# Endstops.net
KiCad netlist of a schematic drawn in Altium Designer
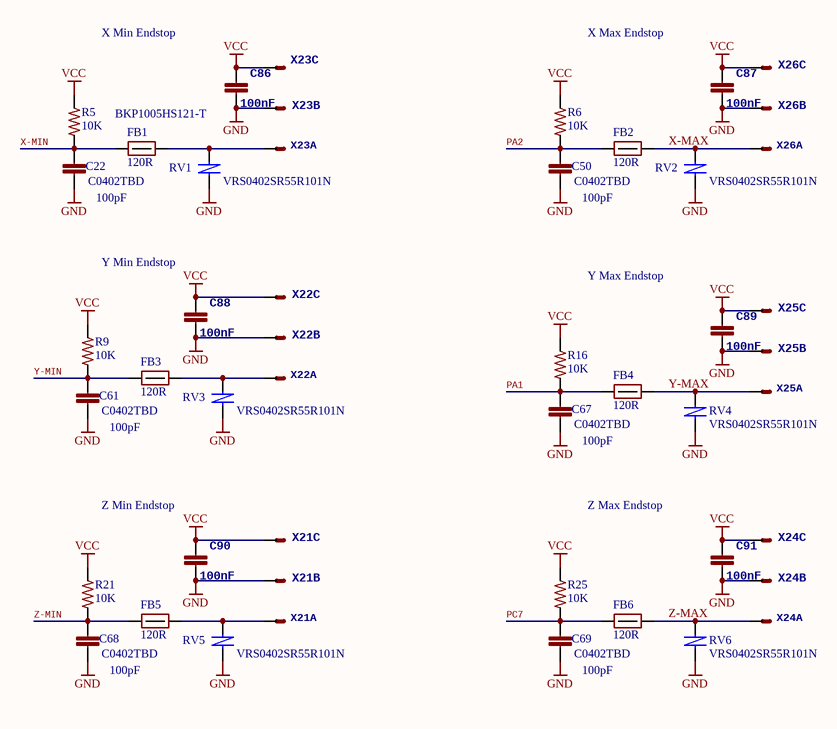
[diagram p0: Endstops.SchDoc]

(export (version "E")
  (design (tool "Eeschema 10.0.6"))
  (components
    (comp (ref "C22")
      (value "100pF")
      (footprint "C0402")
      (description "Capacitor Non Polarized")
      (fields
        (field (name "MANUFACTURER") "Murata")
        (field (name "ALTIUM_VALUE") "C0402TBD")
        (field (name "PUBLISHER") "UltiMachine")
      )
      (libsource (lib "3Delight") (part "C0402TBD"))
    )
    (comp (ref "C50")
      (value "100pF")
      (footprint "C0402")
      (description "Capacitor Non Polarized")
      (fields
        (field (name "MANUFACTURER") "Murata")
        (field (name "ALTIUM_VALUE") "C0402TBD")
        (field (name "PUBLISHER") "UltiMachine")
      )
      (libsource (lib "3Delight") (part "C0402TBD"))
    )
    (comp (ref "C61")
      (value "100pF")
      (footprint "C0402")
      (description "Capacitor Non Polarized")
      (fields
        (field (name "MANUFACTURER") "Murata")
        (field (name "ALTIUM_VALUE") "C0402TBD")
        (field (name "PUBLISHER") "UltiMachine")
      )
      (libsource (lib "3Delight") (part "C0402TBD"))
    )
    (comp (ref "C67")
      (value "100pF")
      (footprint "C0402")
      (description "Capacitor Non Polarized")
      (fields
        (field (name "MANUFACTURER") "Murata")
        (field (name "ALTIUM_VALUE") "C0402TBD")
        (field (name "PUBLISHER") "UltiMachine")
      )
      (libsource (lib "3Delight") (part "C0402TBD"))
    )
    (comp (ref "C68")
      (value "100pF")
      (footprint "C0402")
      (description "Capacitor Non Polarized")
      (fields
        (field (name "MANUFACTURER") "Murata")
        (field (name "ALTIUM_VALUE") "C0402TBD")
        (field (name "PUBLISHER") "UltiMachine")
      )
      (libsource (lib "3Delight") (part "C0402TBD"))
    )
    (comp (ref "C69")
      (value "100pF")
      (footprint "C0402")
      (description "Capacitor Non Polarized")
      (fields
        (field (name "MANUFACTURER") "Murata")
        (field (name "ALTIUM_VALUE") "C0402TBD")
        (field (name "PUBLISHER") "UltiMachine")
      )
      (libsource (lib "3Delight") (part "C0402TBD"))
    )
    (comp (ref "C86")
      (value "100nF")
      (footprint "C0402")
      (description "CAPACITOR, European symbol")
      (fields (field (name "MANUFACTURER") "Murata"))
      (libsource (lib "rcl") (part "C-EUC0402"))
    )
    (comp (ref "C87")
      (value "100nF")
      (footprint "C0402")
      (description "CAPACITOR, European symbol")
      (fields (field (name "MANUFACTURER") "Murata"))
      (libsource (lib "rcl") (part "C-EUC0402"))
    )
    (comp (ref "C88")
      (value "100nF")
      (footprint "C0402")
      (description "CAPACITOR, European symbol")
      (fields (field (name "MANUFACTURER") "Murata"))
      (libsource (lib "rcl") (part "C-EUC0402"))
    )
    (comp (ref "C89")
      (value "100nF")
      (footprint "C0402")
      (description "CAPACITOR, European symbol")
      (fields (field (name "MANUFACTURER") "Murata"))
      (libsource (lib "rcl") (part "C-EUC0402"))
    )
    (comp (ref "C90")
      (value "100nF")
      (footprint "C0402")
      (description "CAPACITOR, European symbol")
      (fields (field (name "MANUFACTURER") "Murata"))
      (libsource (lib "rcl") (part "C-EUC0402"))
    )
    (comp (ref "C91")
      (value "100nF")
      (footprint "C0402")
      (description "CAPACITOR, European symbol")
      (fields (field (name "MANUFACTURER") "Murata"))
      (libsource (lib "rcl") (part "C-EUC0402"))
    )
    (comp (ref "FB1")
      (value "120R")
      (footprint "R0402")
      (description "FERRITE BEAD 120 OHM 0402 1LN")
      (fields
        (field (name "MANUFACTURER") "Taiyo Yuden")
        (field (name "MANUFACTURER #") "BKP1005HS121-T")
        (field (name "PART") "FERRITE 120R 1A 0402")
      )
      (libsource (lib "Inductors_1") (part "FERRITE 120R 1A 0402"))
    )
    (comp (ref "FB2")
      (value "120R")
      (footprint "R0402")
      (description "FERRITE BEAD 120 OHM 0402 1LN")
      (fields (field (name "MANUFACTURER") "Taiyo Yuden") (field (name "PART") "FERRITE 120R 1A 0402"))
      (libsource (lib "Inductors_1") (part "FERRITE 120R 1A 0402"))
    )
    (comp (ref "FB3")
      (value "120R")
      (footprint "R0402")
      (description "FERRITE BEAD 120 OHM 0402 1LN")
      (fields (field (name "MANUFACTURER") "Taiyo Yuden") (field (name "PART") "FERRITE 120R 1A 0402"))
      (libsource (lib "Inductors_1") (part "FERRITE 120R 1A 0402"))
    )
    (comp (ref "FB4")
      (value "120R")
      (footprint "R0402")
      (description "FERRITE BEAD 120 OHM 0402 1LN")
      (fields (field (name "MANUFACTURER") "Taiyo Yuden") (field (name "PART") "FERRITE 120R 1A 0402"))
      (libsource (lib "Inductors_1") (part "FERRITE 120R 1A 0402"))
    )
    (comp (ref "FB5")
      (value "120R")
      (footprint "R0402")
      (description "FERRITE BEAD 120 OHM 0402 1LN")
      (fields (field (name "MANUFACTURER") "Taiyo Yuden") (field (name "PART") "FERRITE 120R 1A 0402"))
      (libsource (lib "Inductors_1") (part "FERRITE 120R 1A 0402"))
    )
    (comp (ref "FB6")
      (value "120R")
      (footprint "R0402")
      (description "FERRITE BEAD 120 OHM 0402 1LN")
      (fields (field (name "MANUFACTURER") "Taiyo Yuden") (field (name "PART") "FERRITE 120R 1A 0402"))
      (libsource (lib "Inductors_1") (part "FERRITE 120R 1A 0402"))
    )
    (comp (ref "R5")
      (value "10K")
      (footprint "R0402")
      (description "RES SMD 10K OHM 1% 1/16W 0402")
      (fields (field (name "MANUFACTURER") "Yageo") (field (name "PART") "10k 1% 0402"))
      (libsource (lib "3Delight") (part "RC0402FR-0710KP"))
    )
    (comp (ref "R6")
      (value "10K")
      (footprint "R0402")
      (description "RES SMD 10K OHM 1% 1/16W 0402")
      (fields (field (name "MANUFACTURER") "Yageo") (field (name "PART") "10k 1% 0402"))
      (libsource (lib "3Delight") (part "RC0402FR-0710KP"))
    )
    (comp (ref "R9")
      (value "10K")
      (footprint "R0402")
      (description "RES SMD 10K OHM 1% 1/16W 0402")
      (fields (field (name "MANUFACTURER") "Yageo") (field (name "PART") "10k 1% 0402"))
      (libsource (lib "3Delight") (part "RC0402FR-0710KP"))
    )
    (comp (ref "R16")
      (value "10K")
      (footprint "R0402")
      (description "RES SMD 10K OHM 1% 1/16W 0402")
      (fields (field (name "MANUFACTURER") "Yageo") (field (name "PART") "10k 1% 0402"))
      (libsource (lib "3Delight") (part "RC0402FR-0710KP"))
    )
    (comp (ref "R21")
      (value "10K")
      (footprint "R0402")
      (description "RES SMD 10K OHM 1% 1/16W 0402")
      (fields (field (name "MANUFACTURER") "Yageo") (field (name "PART") "10k 1% 0402"))
      (libsource (lib "3Delight") (part "RC0402FR-0710KP"))
    )
    (comp (ref "R25")
      (value "10K")
      (footprint "R0402")
      (description "RES SMD 10K OHM 1% 1/16W 0402")
      (fields (field (name "MANUFACTURER") "Yageo") (field (name "PART") "10k 1% 0402"))
      (libsource (lib "3Delight") (part "RC0402FR-0710KP"))
    )
    (comp (ref "RV1")
      (value "VRS0402SR55R101N")
      (footprint "C0402")
      (description "Multi-Layer Varistor")
      (fields
        (field (name "MANUFACTURER #") "VRS0402SR55R101N")
        (field (name "MANUFACTURER") "Yageo")
        (field (name "PART") "12V")
      )
      (libsource (lib "3Delight") (part "VRS0402SR55R101N"))
    )
    (comp (ref "RV2")
      (value "VRS0402SR55R101N")
      (footprint "C0402")
      (description "Multi-Layer Varistor")
      (fields
        (field (name "MANUFACTURER #") "VRS0402SR55R101N")
        (field (name "MANUFACTURER") "Yageo")
        (field (name "PART") "12V")
      )
      (libsource (lib "3Delight") (part "VRS0402SR55R101N"))
    )
    (comp (ref "RV3")
      (value "VRS0402SR55R101N")
      (footprint "C0402")
      (description "Multi-Layer Varistor")
      (fields
        (field (name "MANUFACTURER #") "VRS0402SR55R101N")
        (field (name "MANUFACTURER") "Yageo")
        (field (name "PART") "12V")
      )
      (libsource (lib "3Delight") (part "VRS0402SR55R101N"))
    )
    (comp (ref "RV4")
      (value "VRS0402SR55R101N")
      (footprint "C0402")
      (description "Multi-Layer Varistor")
      (fields
        (field (name "MANUFACTURER #") "VRS0402SR55R101N")
        (field (name "MANUFACTURER") "Yageo")
        (field (name "PART") "12V")
      )
      (libsource (lib "3Delight") (part "VRS0402SR55R101N"))
    )
    (comp (ref "RV5")
      (value "VRS0402SR55R101N")
      (footprint "C0402")
      (description "Multi-Layer Varistor")
      (fields
        (field (name "MANUFACTURER #") "VRS0402SR55R101N")
        (field (name "MANUFACTURER") "Yageo")
        (field (name "PART") "12V")
      )
      (libsource (lib "3Delight") (part "VRS0402SR55R101N"))
    )
    (comp (ref "RV6")
      (value "VRS0402SR55R101N")
      (footprint "C0402")
      (description "Multi-Layer Varistor")
      (fields
        (field (name "MANUFACTURER #") "VRS0402SR55R101N")
        (field (name "MANUFACTURER") "Yageo")
        (field (name "PART") "12V")
      )
      (libsource (lib "3Delight") (part "VRS0402SR55R101N"))
    )
    (comp (ref "X21")
      (value "C-GRID-03-70543")
      (footprint "70543-03")
      (description "CONNECTOR   wire to board 2.54 mm (0.100\") pitch header")
      (fields (field (name "MANUFACTURER") "Molex"))
      (libsource (lib "con-molex") (part "C-GRID-03-70543"))
    )
    (comp (ref "X22")
      (value "C-GRID-03-70543")
      (footprint "70543-03")
      (description "CONNECTOR   wire to board 2.54 mm (0.100\") pitch header")
      (fields (field (name "MANUFACTURER") "Molex"))
      (libsource (lib "con-molex") (part "C-GRID-03-70543"))
    )
    (comp (ref "X23")
      (value "C-GRID-03-70543")
      (footprint "70543-03")
      (description "CONNECTOR   wire to board 2.54 mm (0.100\") pitch header")
      (fields (field (name "MANUFACTURER") "Molex"))
      (libsource (lib "con-molex") (part "C-GRID-03-70543"))
    )
    (comp (ref "X24")
      (value "C-GRID-03-70543")
      (footprint "70543-03")
      (description "CONNECTOR   wire to board 2.54 mm (0.100\") pitch header")
      (fields (field (name "MANUFACTURER") "Molex"))
      (libsource (lib "con-molex") (part "C-GRID-03-70543"))
    )
    (comp (ref "X25")
      (value "C-GRID-03-70543")
      (footprint "70543-03")
      (description "CONNECTOR   wire to board 2.54 mm (0.100\") pitch header")
      (fields (field (name "MANUFACTURER") "Molex"))
      (libsource (lib "con-molex") (part "C-GRID-03-70543"))
    )
    (comp (ref "X26")
      (value "C-GRID-03-70543")
      (footprint "70543-03")
      (description "CONNECTOR   wire to board 2.54 mm (0.100\") pitch header")
      (fields (field (name "MANUFACTURER") "Molex"))
      (libsource (lib "con-molex") (part "C-GRID-03-70543"))
    )
  )
  (nets
    (net (code "1") (name "/PA1") (class "Default")
      (node (ref "C67") (pin "1") (pinfunction "1_1") (pintype "passive"))
      (node (ref "FB4") (pin "1") (pinfunction "1_1") (pintype "passive"))
      (node (ref "R16") (pin "2") (pinfunction "2_2") (pintype "passive"))
    )
    (net (code "2") (name "/PA2") (class "Default")
      (node (ref "C50") (pin "1") (pinfunction "1_1") (pintype "passive"))
      (node (ref "FB2") (pin "1") (pinfunction "1_1") (pintype "passive"))
      (node (ref "R6") (pin "2") (pinfunction "2_2") (pintype "passive"))
    )
    (net (code "3") (name "/PC7") (class "Default")
      (node (ref "C69") (pin "1") (pinfunction "1_1") (pintype "passive"))
      (node (ref "FB6") (pin "1") (pinfunction "1_1") (pintype "passive"))
      (node (ref "R25") (pin "2") (pinfunction "2_2") (pintype "passive"))
    )
    (net (code "4") (name "/X-MAX") (class "Default")
      (node (ref "FB2") (pin "2") (pinfunction "2_2") (pintype "passive"))
      (node (ref "RV2") (pin "2") (pinfunction "2_2") (pintype "passive"))
      (node (ref "X26") (pin "1") (pinfunction "S_1") (pintype "passive"))
    )
    (net (code "5") (name "/X-MIN") (class "Default")
      (node (ref "C22") (pin "1") (pinfunction "1_1") (pintype "passive"))
      (node (ref "FB1") (pin "1") (pinfunction "1_1") (pintype "passive"))
      (node (ref "R5") (pin "2") (pinfunction "2_2") (pintype "passive"))
    )
    (net (code "6") (name "/Y-MAX") (class "Default")
      (node (ref "FB4") (pin "2") (pinfunction "2_2") (pintype "passive"))
      (node (ref "RV4") (pin "2") (pinfunction "2_2") (pintype "passive"))
      (node (ref "X25") (pin "1") (pinfunction "S_1") (pintype "passive"))
    )
    (net (code "7") (name "/Y-MIN") (class "Default")
      (node (ref "C61") (pin "1") (pinfunction "1_1") (pintype "passive"))
      (node (ref "FB3") (pin "1") (pinfunction "1_1") (pintype "passive"))
      (node (ref "R9") (pin "2") (pinfunction "2_2") (pintype "passive"))
    )
    (net (code "8") (name "/Z-MAX") (class "Default")
      (node (ref "FB6") (pin "2") (pinfunction "2_2") (pintype "passive"))
      (node (ref "RV6") (pin "2") (pinfunction "2_2") (pintype "passive"))
      (node (ref "X24") (pin "1") (pinfunction "S_1") (pintype "passive"))
    )
    (net (code "9") (name "/Z-MIN") (class "Default")
      (node (ref "C68") (pin "1") (pinfunction "1_1") (pintype "passive"))
      (node (ref "FB5") (pin "1") (pinfunction "1_1") (pintype "passive"))
      (node (ref "R21") (pin "2") (pinfunction "2_2") (pintype "passive"))
    )
    (net (code "10") (name "GND") (class "Default")
      (node (ref "C22") (pin "2") (pinfunction "2_2") (pintype "passive"))
      (node (ref "C50") (pin "2") (pinfunction "2_2") (pintype "passive"))
      (node (ref "C61") (pin "2") (pinfunction "2_2") (pintype "passive"))
      (node (ref "C67") (pin "2") (pinfunction "2_2") (pintype "passive"))
      (node (ref "C68") (pin "2") (pinfunction "2_2") (pintype "passive"))
      (node (ref "C69") (pin "2") (pinfunction "2_2") (pintype "passive"))
      (node (ref "C86") (pin "1") (pinfunction "1_1") (pintype "passive"))
      (node (ref "C87") (pin "1") (pinfunction "1_1") (pintype "passive"))
      (node (ref "C88") (pin "1") (pinfunction "1_1") (pintype "passive"))
      (node (ref "C89") (pin "1") (pinfunction "1_1") (pintype "passive"))
      (node (ref "C90") (pin "1") (pinfunction "1_1") (pintype "passive"))
      (node (ref "C91") (pin "1") (pinfunction "1_1") (pintype "passive"))
      (node (ref "RV1") (pin "1") (pinfunction "1_1") (pintype "passive"))
      (node (ref "RV2") (pin "1") (pinfunction "1_1") (pintype "passive"))
      (node (ref "RV3") (pin "1") (pinfunction "1_1") (pintype "passive"))
      (node (ref "RV4") (pin "1") (pinfunction "1_1") (pintype "passive"))
      (node (ref "RV5") (pin "1") (pinfunction "1_1") (pintype "passive"))
      (node (ref "RV6") (pin "1") (pinfunction "1_1") (pintype "passive"))
      (node (ref "X21") (pin "2") (pinfunction "S_2") (pintype "passive"))
      (node (ref "X22") (pin "2") (pinfunction "S_2") (pintype "passive"))
      (node (ref "X23") (pin "2") (pinfunction "S_2") (pintype "passive"))
      (node (ref "X24") (pin "2") (pinfunction "S_2") (pintype "passive"))
      (node (ref "X25") (pin "2") (pinfunction "S_2") (pintype "passive"))
      (node (ref "X26") (pin "2") (pinfunction "S_2") (pintype "passive"))
    )
    (net (code "11") (name "Net-(X21A-S)") (class "Default")
      (node (ref "FB5") (pin "2") (pinfunction "2_2") (pintype "passive"))
      (node (ref "RV5") (pin "2") (pinfunction "2_2") (pintype "passive"))
      (node (ref "X21") (pin "1") (pinfunction "S_1") (pintype "passive"))
    )
    (net (code "12") (name "Net-(X22A-S)") (class "Default")
      (node (ref "FB3") (pin "2") (pinfunction "2_2") (pintype "passive"))
      (node (ref "RV3") (pin "2") (pinfunction "2_2") (pintype "passive"))
      (node (ref "X22") (pin "1") (pinfunction "S_1") (pintype "passive"))
    )
    (net (code "13") (name "Net-(X23A-S)") (class "Default")
      (node (ref "FB1") (pin "2") (pinfunction "2_2") (pintype "passive"))
      (node (ref "RV1") (pin "2") (pinfunction "2_2") (pintype "passive"))
      (node (ref "X23") (pin "1") (pinfunction "S_1") (pintype "passive"))
    )
    (net (code "14") (name "VCC") (class "Default")
      (node (ref "C86") (pin "2") (pinfunction "2_2") (pintype "passive"))
      (node (ref "C87") (pin "2") (pinfunction "2_2") (pintype "passive"))
      (node (ref "C88") (pin "2") (pinfunction "2_2") (pintype "passive"))
      (node (ref "C89") (pin "2") (pinfunction "2_2") (pintype "passive"))
      (node (ref "C90") (pin "2") (pinfunction "2_2") (pintype "passive"))
      (node (ref "C91") (pin "2") (pinfunction "2_2") (pintype "passive"))
      (node (ref "R16") (pin "1") (pinfunction "1_1") (pintype "passive"))
      (node (ref "R21") (pin "1") (pinfunction "1_1") (pintype "passive"))
      (node (ref "R25") (pin "1") (pinfunction "1_1") (pintype "passive"))
      (node (ref "R5") (pin "1") (pinfunction "1_1") (pintype "passive"))
      (node (ref "R6") (pin "1") (pinfunction "1_1") (pintype "passive"))
      (node (ref "R9") (pin "1") (pinfunction "1_1") (pintype "passive"))
      (node (ref "X21") (pin "3") (pinfunction "S_3") (pintype "passive"))
      (node (ref "X22") (pin "3") (pinfunction "S_3") (pintype "passive"))
      (node (ref "X23") (pin "3") (pinfunction "S_3") (pintype "passive"))
      (node (ref "X24") (pin "3") (pinfunction "S_3") (pintype "passive"))
      (node (ref "X25") (pin "3") (pinfunction "S_3") (pintype "passive"))
      (node (ref "X26") (pin "3") (pinfunction "S_3") (pintype "passive"))
    )
  )
)
